# ArduinoPCB.net
KiCad netlist of a schematic drawn in EAGLE
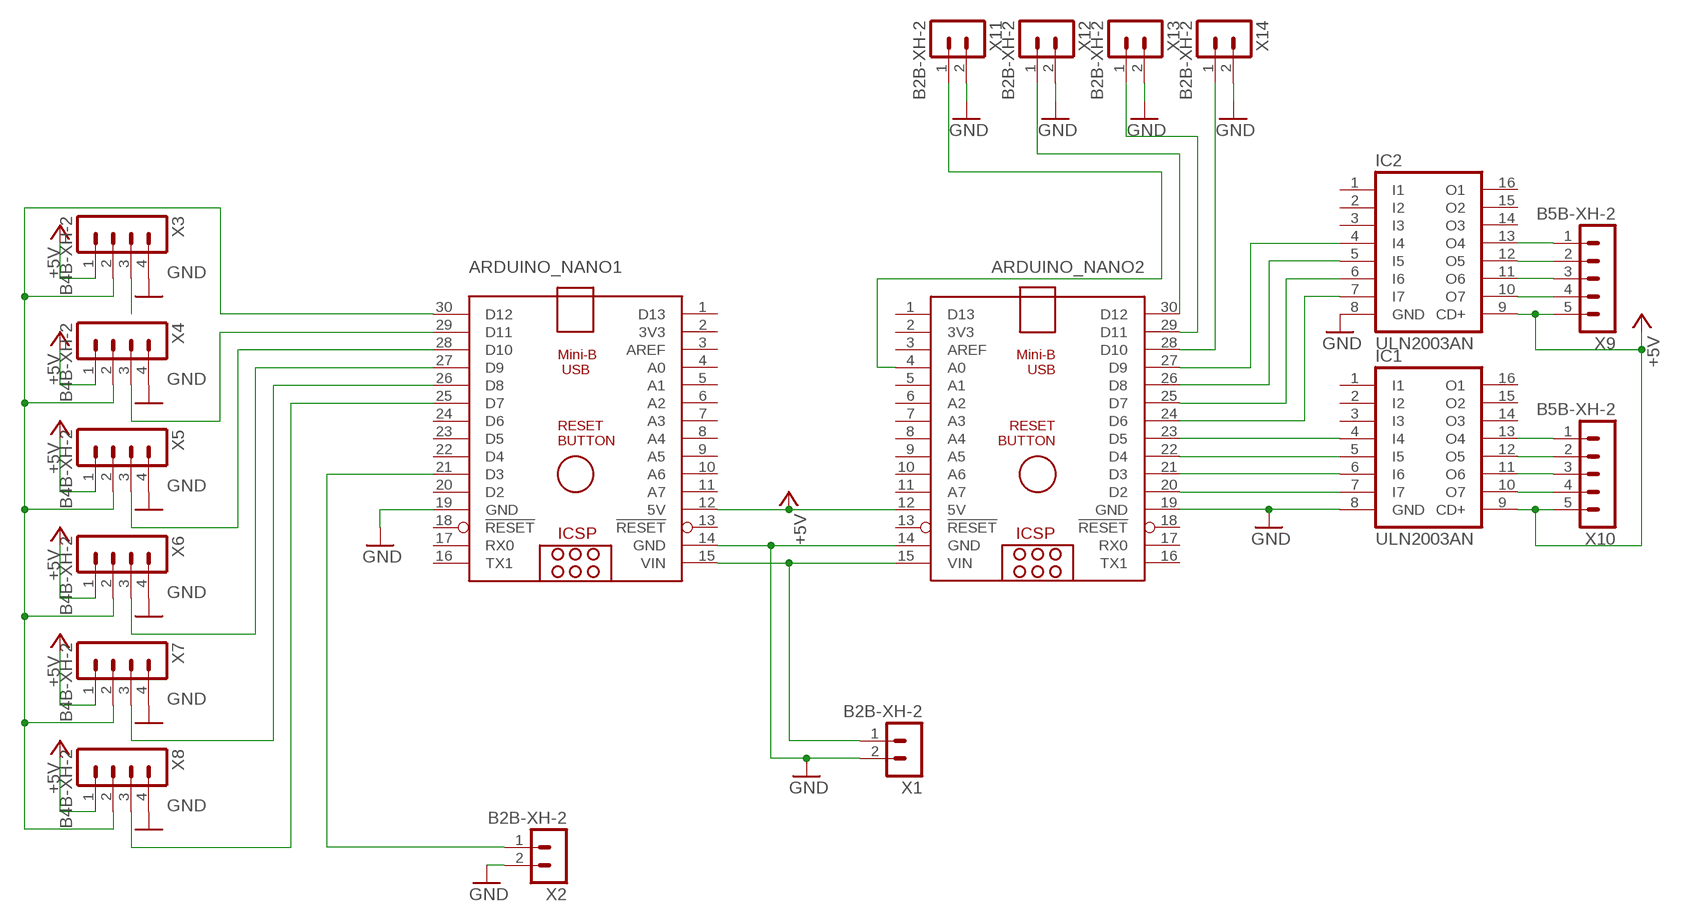
[diagram p0: schematic, sheet 1]

(export (version "E")
  (design (tool "Eeschema 10.0.6"))
  (components
    (comp (ref "ARDUINO_NANO1")
      (value "ARDUINO_NANO")
      (footprint "eagle-import:ARDUINO_NANO")
      (libsource (lib "eagle-import") (part "ARDUINO_NANO"))
    )
    (comp (ref "ARDUINO_NANO2")
      (value "ARDUINO_NANO")
      (footprint "eagle-import:ARDUINO_NANO")
      (libsource (lib "eagle-import") (part "ARDUINO_NANO"))
    )
    (comp (ref "IC1")
      (value "ULN2003AN")
      (footprint "eagle-import:DIL16")
      (libsource (lib "eagle-import") (part "ULN2003AN"))
    )
    (comp (ref "IC2")
      (value "ULN2003AN")
      (footprint "eagle-import:DIL16")
      (libsource (lib "eagle-import") (part "ULN2003AN"))
    )
    (comp (ref "X1")
      (value "B2B-XH-2")
      (footprint "eagle-import:B2B-XH-A")
      (libsource (lib "eagle-import") (part "B2B-XH-2"))
    )
    (comp (ref "X2")
      (value "B2B-XH-2")
      (footprint "eagle-import:B2B-XH-A")
      (libsource (lib "eagle-import") (part "B2B-XH-2"))
    )
    (comp (ref "X3")
      (value "B4B-XH-2")
      (footprint "eagle-import:B4B-XH-A")
      (libsource (lib "eagle-import") (part "B4B-XH-2"))
    )
    (comp (ref "X4")
      (value "B4B-XH-2")
      (footprint "eagle-import:B4B-XH-A")
      (libsource (lib "eagle-import") (part "B4B-XH-2"))
    )
    (comp (ref "X5")
      (value "B4B-XH-2")
      (footprint "eagle-import:B4B-XH-A")
      (libsource (lib "eagle-import") (part "B4B-XH-2"))
    )
    (comp (ref "X6")
      (value "B4B-XH-2")
      (footprint "eagle-import:B4B-XH-A")
      (libsource (lib "eagle-import") (part "B4B-XH-2"))
    )
    (comp (ref "X7")
      (value "B4B-XH-2")
      (footprint "eagle-import:B4B-XH-A")
      (libsource (lib "eagle-import") (part "B4B-XH-2"))
    )
    (comp (ref "X8")
      (value "B4B-XH-2")
      (footprint "eagle-import:B4B-XH-A")
      (libsource (lib "eagle-import") (part "B4B-XH-2"))
    )
    (comp (ref "X9")
      (value "B5B-XH-2")
      (footprint "eagle-import:B5B-XH-A")
      (libsource (lib "eagle-import") (part "B5B-XH-2"))
    )
    (comp (ref "X10")
      (value "B5B-XH-2")
      (footprint "eagle-import:B5B-XH-A")
      (libsource (lib "eagle-import") (part "B5B-XH-2"))
    )
    (comp (ref "X11")
      (value "B2B-XH-2")
      (footprint "eagle-import:B2B-XH-A")
      (libsource (lib "eagle-import") (part "B2B-XH-2"))
    )
    (comp (ref "X12")
      (value "B2B-XH-2")
      (footprint "eagle-import:B2B-XH-A")
      (libsource (lib "eagle-import") (part "B2B-XH-2"))
    )
    (comp (ref "X13")
      (value "B2B-XH-2")
      (footprint "eagle-import:B2B-XH-A")
      (libsource (lib "eagle-import") (part "B2B-XH-2"))
    )
    (comp (ref "X14")
      (value "B2B-XH-2")
      (footprint "eagle-import:B2B-XH-A")
      (libsource (lib "eagle-import") (part "B2B-XH-2"))
    )
  )
  (nets
    (net (code "1") (name "+5V") (class "Default")
      (node (ref "ARDUINO_NANO1") (pin "12") (pinfunction "5V_12") (pintype "power_in"))
      (node (ref "ARDUINO_NANO2") (pin "12") (pinfunction "5V_12") (pintype "power_in"))
      (node (ref "IC1") (pin "9") (pinfunction "CD+_9") (pintype "passive"))
      (node (ref "IC2") (pin "9") (pinfunction "CD+_9") (pintype "passive"))
      (node (ref "X10") (pin "5") (pinfunction "5_5") (pintype "passive"))
      (node (ref "X3") (pin "1") (pinfunction "1_1") (pintype "passive"))
      (node (ref "X4") (pin "1") (pinfunction "1_1") (pintype "passive"))
      (node (ref "X5") (pin "1") (pinfunction "1_1") (pintype "passive"))
      (node (ref "X6") (pin "1") (pinfunction "1_1") (pintype "passive"))
      (node (ref "X7") (pin "1") (pinfunction "1_1") (pintype "passive"))
      (node (ref "X8") (pin "1") (pinfunction "1_1") (pintype "passive"))
      (node (ref "X9") (pin "5") (pinfunction "5_5") (pintype "passive"))
    )
    (net (code "2") (name "GND") (class "Default")
      (node (ref "ARDUINO_NANO1") (pin "14") (pinfunction "GND_14") (pintype "power_in"))
      (node (ref "ARDUINO_NANO1") (pin "19") (pinfunction "GND_19") (pintype "power_in"))
      (node (ref "ARDUINO_NANO2") (pin "14") (pinfunction "GND_14") (pintype "power_in"))
      (node (ref "ARDUINO_NANO2") (pin "19") (pinfunction "GND_19") (pintype "power_in"))
      (node (ref "IC1") (pin "8") (pinfunction "GND_8") (pintype "power_in"))
      (node (ref "IC2") (pin "8") (pinfunction "GND_8") (pintype "power_in"))
      (node (ref "X1") (pin "2") (pinfunction "2_2") (pintype "passive"))
      (node (ref "X11") (pin "2") (pinfunction "2_2") (pintype "passive"))
      (node (ref "X12") (pin "2") (pinfunction "2_2") (pintype "passive"))
      (node (ref "X13") (pin "2") (pinfunction "2_2") (pintype "passive"))
      (node (ref "X14") (pin "2") (pinfunction "2_2") (pintype "passive"))
      (node (ref "X2") (pin "2") (pinfunction "2_2") (pintype "passive"))
      (node (ref "X3") (pin "4") (pinfunction "4_4") (pintype "passive"))
      (node (ref "X4") (pin "4") (pinfunction "4_4") (pintype "passive"))
      (node (ref "X5") (pin "4") (pinfunction "4_4") (pintype "passive"))
      (node (ref "X6") (pin "4") (pinfunction "4_4") (pintype "passive"))
      (node (ref "X7") (pin "4") (pinfunction "4_4") (pintype "passive"))
      (node (ref "X8") (pin "4") (pinfunction "4_4") (pintype "passive"))
    )
    (net (code "3") (name "Net-(ARDUINO_NANO1-D3)") (class "Default")
      (node (ref "ARDUINO_NANO1") (pin "21") (pinfunction "D3_21") (pintype "bidirectional"))
      (node (ref "X2") (pin "1") (pinfunction "1_1") (pintype "passive"))
    )
    (net (code "4") (name "Net-(ARDUINO_NANO1-D7)") (class "Default")
      (node (ref "ARDUINO_NANO1") (pin "25") (pinfunction "D7_25") (pintype "bidirectional"))
      (node (ref "X8") (pin "3") (pinfunction "3_3") (pintype "passive"))
    )
    (net (code "5") (name "Net-(ARDUINO_NANO1-D8)") (class "Default")
      (node (ref "ARDUINO_NANO1") (pin "26") (pinfunction "D8_26") (pintype "bidirectional"))
      (node (ref "X7") (pin "3") (pinfunction "3_3") (pintype "passive"))
    )
    (net (code "6") (name "Net-(ARDUINO_NANO1-D9)") (class "Default")
      (node (ref "ARDUINO_NANO1") (pin "27") (pinfunction "D9_27") (pintype "bidirectional"))
      (node (ref "X6") (pin "3") (pinfunction "3_3") (pintype "passive"))
    )
    (net (code "7") (name "Net-(ARDUINO_NANO1-D10)") (class "Default")
      (node (ref "ARDUINO_NANO1") (pin "28") (pinfunction "D10_28") (pintype "bidirectional"))
      (node (ref "X5") (pin "3") (pinfunction "3_3") (pintype "passive"))
    )
    (net (code "8") (name "Net-(ARDUINO_NANO1-D11)") (class "Default")
      (node (ref "ARDUINO_NANO1") (pin "29") (pinfunction "D11_29") (pintype "bidirectional"))
      (node (ref "X4") (pin "3") (pinfunction "3_3") (pintype "passive"))
    )
    (net (code "9") (name "Net-(ARDUINO_NANO1-D12)") (class "Default")
      (node (ref "ARDUINO_NANO1") (pin "30") (pinfunction "D12_30") (pintype "bidirectional"))
      (node (ref "X3") (pin "2") (pinfunction "2_2") (pintype "passive"))
      (node (ref "X4") (pin "2") (pinfunction "2_2") (pintype "passive"))
      (node (ref "X5") (pin "2") (pinfunction "2_2") (pintype "passive"))
      (node (ref "X6") (pin "2") (pinfunction "2_2") (pintype "passive"))
      (node (ref "X7") (pin "2") (pinfunction "2_2") (pintype "passive"))
      (node (ref "X8") (pin "2") (pinfunction "2_2") (pintype "passive"))
    )
    (net (code "10") (name "Net-(ARDUINO_NANO1-VIN)") (class "Default")
      (node (ref "ARDUINO_NANO1") (pin "15") (pinfunction "VIN_15") (pintype "power_in"))
      (node (ref "ARDUINO_NANO2") (pin "15") (pinfunction "VIN_15") (pintype "power_in"))
      (node (ref "X1") (pin "1") (pinfunction "1_1") (pintype "passive"))
    )
    (net (code "11") (name "Net-(ARDUINO_NANO2-A0)") (class "Default")
      (node (ref "ARDUINO_NANO2") (pin "4") (pinfunction "A0_4") (pintype "bidirectional"))
      (node (ref "X11") (pin "1") (pinfunction "1_1") (pintype "passive"))
    )
    (net (code "12") (name "Net-(ARDUINO_NANO2-D2)") (class "Default")
      (node (ref "ARDUINO_NANO2") (pin "20") (pinfunction "D2_20") (pintype "bidirectional"))
      (node (ref "IC1") (pin "7") (pinfunction "I7_7") (pintype "input"))
    )
    (net (code "13") (name "Net-(ARDUINO_NANO2-D3)") (class "Default")
      (node (ref "ARDUINO_NANO2") (pin "21") (pinfunction "D3_21") (pintype "bidirectional"))
      (node (ref "IC1") (pin "6") (pinfunction "I6_6") (pintype "input"))
    )
    (net (code "14") (name "Net-(ARDUINO_NANO2-D4)") (class "Default")
      (node (ref "ARDUINO_NANO2") (pin "22") (pinfunction "D4_22") (pintype "bidirectional"))
      (node (ref "IC1") (pin "5") (pinfunction "I5_5") (pintype "input"))
    )
    (net (code "15") (name "Net-(ARDUINO_NANO2-D5)") (class "Default")
      (node (ref "ARDUINO_NANO2") (pin "23") (pinfunction "D5_23") (pintype "bidirectional"))
      (node (ref "IC1") (pin "4") (pinfunction "I4_4") (pintype "input"))
    )
    (net (code "16") (name "Net-(ARDUINO_NANO2-D6)") (class "Default")
      (node (ref "ARDUINO_NANO2") (pin "24") (pinfunction "D6_24") (pintype "bidirectional"))
      (node (ref "IC2") (pin "7") (pinfunction "I7_7") (pintype "input"))
    )
    (net (code "17") (name "Net-(ARDUINO_NANO2-D7)") (class "Default")
      (node (ref "ARDUINO_NANO2") (pin "25") (pinfunction "D7_25") (pintype "bidirectional"))
      (node (ref "IC2") (pin "6") (pinfunction "I6_6") (pintype "input"))
    )
    (net (code "18") (name "Net-(ARDUINO_NANO2-D8)") (class "Default")
      (node (ref "ARDUINO_NANO2") (pin "26") (pinfunction "D8_26") (pintype "bidirectional"))
      (node (ref "IC2") (pin "5") (pinfunction "I5_5") (pintype "input"))
    )
    (net (code "19") (name "Net-(ARDUINO_NANO2-D9)") (class "Default")
      (node (ref "ARDUINO_NANO2") (pin "27") (pinfunction "D9_27") (pintype "bidirectional"))
      (node (ref "IC2") (pin "4") (pinfunction "I4_4") (pintype "input"))
    )
    (net (code "20") (name "Net-(ARDUINO_NANO2-D10)") (class "Default")
      (node (ref "ARDUINO_NANO2") (pin "28") (pinfunction "D10_28") (pintype "bidirectional"))
      (node (ref "X14") (pin "1") (pinfunction "1_1") (pintype "passive"))
    )
    (net (code "21") (name "Net-(ARDUINO_NANO2-D11)") (class "Default")
      (node (ref "ARDUINO_NANO2") (pin "29") (pinfunction "D11_29") (pintype "bidirectional"))
      (node (ref "X13") (pin "1") (pinfunction "1_1") (pintype "passive"))
    )
    (net (code "22") (name "Net-(ARDUINO_NANO2-D12)") (class "Default")
      (node (ref "ARDUINO_NANO2") (pin "30") (pinfunction "D12_30") (pintype "bidirectional"))
      (node (ref "X12") (pin "1") (pinfunction "1_1") (pintype "passive"))
    )
    (net (code "23") (name "Net-(IC1-O4)") (class "Default")
      (node (ref "IC1") (pin "13") (pinfunction "O4_13") (pintype "open_collector"))
      (node (ref "X10") (pin "1") (pinfunction "1_1") (pintype "passive"))
    )
    (net (code "24") (name "Net-(IC1-O5)") (class "Default")
      (node (ref "IC1") (pin "12") (pinfunction "O5_12") (pintype "open_collector"))
      (node (ref "X10") (pin "2") (pinfunction "2_2") (pintype "passive"))
    )
    (net (code "25") (name "Net-(IC1-O6)") (class "Default")
      (node (ref "IC1") (pin "11") (pinfunction "O6_11") (pintype "open_collector"))
      (node (ref "X10") (pin "3") (pinfunction "3_3") (pintype "passive"))
    )
    (net (code "26") (name "Net-(IC1-O7)") (class "Default")
      (node (ref "IC1") (pin "10") (pinfunction "O7_10") (pintype "open_collector"))
      (node (ref "X10") (pin "4") (pinfunction "4_4") (pintype "passive"))
    )
    (net (code "27") (name "Net-(IC2-O4)") (class "Default")
      (node (ref "IC2") (pin "13") (pinfunction "O4_13") (pintype "open_collector"))
      (node (ref "X9") (pin "1") (pinfunction "1_1") (pintype "passive"))
    )
    (net (code "28") (name "Net-(IC2-O5)") (class "Default")
      (node (ref "IC2") (pin "12") (pinfunction "O5_12") (pintype "open_collector"))
      (node (ref "X9") (pin "2") (pinfunction "2_2") (pintype "passive"))
    )
    (net (code "29") (name "Net-(IC2-O6)") (class "Default")
      (node (ref "IC2") (pin "11") (pinfunction "O6_11") (pintype "open_collector"))
      (node (ref "X9") (pin "3") (pinfunction "3_3") (pintype "passive"))
    )
    (net (code "30") (name "Net-(IC2-O7)") (class "Default")
      (node (ref "IC2") (pin "10") (pinfunction "O7_10") (pintype "open_collector"))
      (node (ref "X9") (pin "4") (pinfunction "4_4") (pintype "passive"))
    )
    (net (code "31") (name "unconnected-(ARDUINO_NANO1-3V3-Pad2)") (class "Default")
      (node (ref "ARDUINO_NANO1") (pin "2") (pinfunction "3V3_2") (pintype "output"))
    )
    (net (code "32") (name "unconnected-(ARDUINO_NANO1-A0-Pad4)") (class "Default")
      (node (ref "ARDUINO_NANO1") (pin "4") (pinfunction "A0_4") (pintype "bidirectional"))
    )
    (net (code "33") (name "unconnected-(ARDUINO_NANO1-A1-Pad5)") (class "Default")
      (node (ref "ARDUINO_NANO1") (pin "5") (pinfunction "A1_5") (pintype "bidirectional"))
    )
    (net (code "34") (name "unconnected-(ARDUINO_NANO1-A2-Pad6)") (class "Default")
      (node (ref "ARDUINO_NANO1") (pin "6") (pinfunction "A2_6") (pintype "bidirectional"))
    )
    (net (code "35") (name "unconnected-(ARDUINO_NANO1-A3-Pad7)") (class "Default")
      (node (ref "ARDUINO_NANO1") (pin "7") (pinfunction "A3_7") (pintype "bidirectional"))
    )
    (net (code "36") (name "unconnected-(ARDUINO_NANO1-A4-Pad8)") (class "Default")
      (node (ref "ARDUINO_NANO1") (pin "8") (pinfunction "A4_8") (pintype "bidirectional"))
    )
    (net (code "37") (name "unconnected-(ARDUINO_NANO1-A5-Pad9)") (class "Default")
      (node (ref "ARDUINO_NANO1") (pin "9") (pinfunction "A5_9") (pintype "bidirectional"))
    )
    (net (code "38") (name "unconnected-(ARDUINO_NANO1-A6-Pad10)") (class "Default")
      (node (ref "ARDUINO_NANO1") (pin "10") (pinfunction "A6_10") (pintype "bidirectional"))
    )
    (net (code "39") (name "unconnected-(ARDUINO_NANO1-A7-Pad11)") (class "Default")
      (node (ref "ARDUINO_NANO1") (pin "11") (pinfunction "A7_11") (pintype "bidirectional"))
    )
    (net (code "40") (name "unconnected-(ARDUINO_NANO1-AREF-Pad3)") (class "Default")
      (node (ref "ARDUINO_NANO1") (pin "3") (pinfunction "AREF_3") (pintype "input"))
    )
    (net (code "41") (name "unconnected-(ARDUINO_NANO1-D2-Pad20)") (class "Default")
      (node (ref "ARDUINO_NANO1") (pin "20") (pinfunction "D2_20") (pintype "bidirectional"))
    )
    (net (code "42") (name "unconnected-(ARDUINO_NANO1-D4-Pad22)") (class "Default")
      (node (ref "ARDUINO_NANO1") (pin "22") (pinfunction "D4_22") (pintype "bidirectional"))
    )
    (net (code "43") (name "unconnected-(ARDUINO_NANO1-D5-Pad23)") (class "Default")
      (node (ref "ARDUINO_NANO1") (pin "23") (pinfunction "D5_23") (pintype "bidirectional"))
    )
    (net (code "44") (name "unconnected-(ARDUINO_NANO1-D6-Pad24)") (class "Default")
      (node (ref "ARDUINO_NANO1") (pin "24") (pinfunction "D6_24") (pintype "bidirectional"))
    )
    (net (code "45") (name "unconnected-(ARDUINO_NANO1-D13-Pad1)") (class "Default")
      (node (ref "ARDUINO_NANO1") (pin "1") (pinfunction "D13_1") (pintype "bidirectional"))
    )
    (net (code "46") (name "unconnected-(ARDUINO_NANO1-RX0-Pad17)") (class "Default")
      (node (ref "ARDUINO_NANO1") (pin "17") (pinfunction "RX0_17") (pintype "bidirectional"))
    )
    (net (code "47") (name "unconnected-(ARDUINO_NANO1-TX1-Pad16)") (class "Default")
      (node (ref "ARDUINO_NANO1") (pin "16") (pinfunction "TX1_16") (pintype "bidirectional"))
    )
    (net (code "48") (name "unconnected-(ARDUINO_NANO1-~{RESET}-Pad13)") (class "Default")
      (node (ref "ARDUINO_NANO1") (pin "13") (pinfunction "~{RESET}_13") (pintype "input"))
    )
    (net (code "49") (name "unconnected-(ARDUINO_NANO1-~{RESET}-Pad18)") (class "Default")
      (node (ref "ARDUINO_NANO1") (pin "18") (pinfunction "~{RESET}_18") (pintype "input"))
    )
    (net (code "50") (name "unconnected-(ARDUINO_NANO2-3V3-Pad2)") (class "Default")
      (node (ref "ARDUINO_NANO2") (pin "2") (pinfunction "3V3_2") (pintype "output"))
    )
    (net (code "51") (name "unconnected-(ARDUINO_NANO2-A1-Pad5)") (class "Default")
      (node (ref "ARDUINO_NANO2") (pin "5") (pinfunction "A1_5") (pintype "bidirectional"))
    )
    (net (code "52") (name "unconnected-(ARDUINO_NANO2-A2-Pad6)") (class "Default")
      (node (ref "ARDUINO_NANO2") (pin "6") (pinfunction "A2_6") (pintype "bidirectional"))
    )
    (net (code "53") (name "unconnected-(ARDUINO_NANO2-A3-Pad7)") (class "Default")
      (node (ref "ARDUINO_NANO2") (pin "7") (pinfunction "A3_7") (pintype "bidirectional"))
    )
    (net (code "54") (name "unconnected-(ARDUINO_NANO2-A4-Pad8)") (class "Default")
      (node (ref "ARDUINO_NANO2") (pin "8") (pinfunction "A4_8") (pintype "bidirectional"))
    )
    (net (code "55") (name "unconnected-(ARDUINO_NANO2-A5-Pad9)") (class "Default")
      (node (ref "ARDUINO_NANO2") (pin "9") (pinfunction "A5_9") (pintype "bidirectional"))
    )
    (net (code "56") (name "unconnected-(ARDUINO_NANO2-A6-Pad10)") (class "Default")
      (node (ref "ARDUINO_NANO2") (pin "10") (pinfunction "A6_10") (pintype "bidirectional"))
    )
    (net (code "57") (name "unconnected-(ARDUINO_NANO2-A7-Pad11)") (class "Default")
      (node (ref "ARDUINO_NANO2") (pin "11") (pinfunction "A7_11") (pintype "bidirectional"))
    )
    (net (code "58") (name "unconnected-(ARDUINO_NANO2-AREF-Pad3)") (class "Default")
      (node (ref "ARDUINO_NANO2") (pin "3") (pinfunction "AREF_3") (pintype "input"))
    )
    (net (code "59") (name "unconnected-(ARDUINO_NANO2-D13-Pad1)") (class "Default")
      (node (ref "ARDUINO_NANO2") (pin "1") (pinfunction "D13_1") (pintype "bidirectional"))
    )
    (net (code "60") (name "unconnected-(ARDUINO_NANO2-RX0-Pad17)") (class "Default")
      (node (ref "ARDUINO_NANO2") (pin "17") (pinfunction "RX0_17") (pintype "bidirectional"))
    )
    (net (code "61") (name "unconnected-(ARDUINO_NANO2-TX1-Pad16)") (class "Default")
      (node (ref "ARDUINO_NANO2") (pin "16") (pinfunction "TX1_16") (pintype "bidirectional"))
    )
    (net (code "62") (name "unconnected-(ARDUINO_NANO2-~{RESET}-Pad13)") (class "Default")
      (node (ref "ARDUINO_NANO2") (pin "13") (pinfunction "~{RESET}_13") (pintype "input"))
    )
    (net (code "63") (name "unconnected-(ARDUINO_NANO2-~{RESET}-Pad18)") (class "Default")
      (node (ref "ARDUINO_NANO2") (pin "18") (pinfunction "~{RESET}_18") (pintype "input"))
    )
    (net (code "64") (name "unconnected-(IC1-I1-Pad1)") (class "Default")
      (node (ref "IC1") (pin "1") (pinfunction "I1_1") (pintype "input"))
    )
    (net (code "65") (name "unconnected-(IC1-I2-Pad2)") (class "Default")
      (node (ref "IC1") (pin "2") (pinfunction "I2_2") (pintype "input"))
    )
    (net (code "66") (name "unconnected-(IC1-I3-Pad3)") (class "Default")
      (node (ref "IC1") (pin "3") (pinfunction "I3_3") (pintype "input"))
    )
    (net (code "67") (name "unconnected-(IC1-O1-Pad16)") (class "Default")
      (node (ref "IC1") (pin "16") (pinfunction "O1_16") (pintype "open_collector"))
    )
    (net (code "68") (name "unconnected-(IC1-O2-Pad15)") (class "Default")
      (node (ref "IC1") (pin "15") (pinfunction "O2_15") (pintype "open_collector"))
    )
    (net (code "69") (name "unconnected-(IC1-O3-Pad14)") (class "Default")
      (node (ref "IC1") (pin "14") (pinfunction "O3_14") (pintype "open_collector"))
    )
    (net (code "70") (name "unconnected-(IC2-I1-Pad1)") (class "Default")
      (node (ref "IC2") (pin "1") (pinfunction "I1_1") (pintype "input"))
    )
    (net (code "71") (name "unconnected-(IC2-I2-Pad2)") (class "Default")
      (node (ref "IC2") (pin "2") (pinfunction "I2_2") (pintype "input"))
    )
    (net (code "72") (name "unconnected-(IC2-I3-Pad3)") (class "Default")
      (node (ref "IC2") (pin "3") (pinfunction "I3_3") (pintype "input"))
    )
    (net (code "73") (name "unconnected-(IC2-O1-Pad16)") (class "Default")
      (node (ref "IC2") (pin "16") (pinfunction "O1_16") (pintype "open_collector"))
    )
    (net (code "74") (name "unconnected-(IC2-O2-Pad15)") (class "Default")
      (node (ref "IC2") (pin "15") (pinfunction "O2_15") (pintype "open_collector"))
    )
    (net (code "75") (name "unconnected-(IC2-O3-Pad14)") (class "Default")
      (node (ref "IC2") (pin "14") (pinfunction "O3_14") (pintype "open_collector"))
    )
    (net (code "76") (name "unconnected-(X3-Pad3)") (class "Default")
      (node (ref "X3") (pin "3") (pinfunction "3_3") (pintype "passive"))
    )
  )
)
